# RTM_CON.net
KiCad netlist of a schematic drawn in Altium Designer
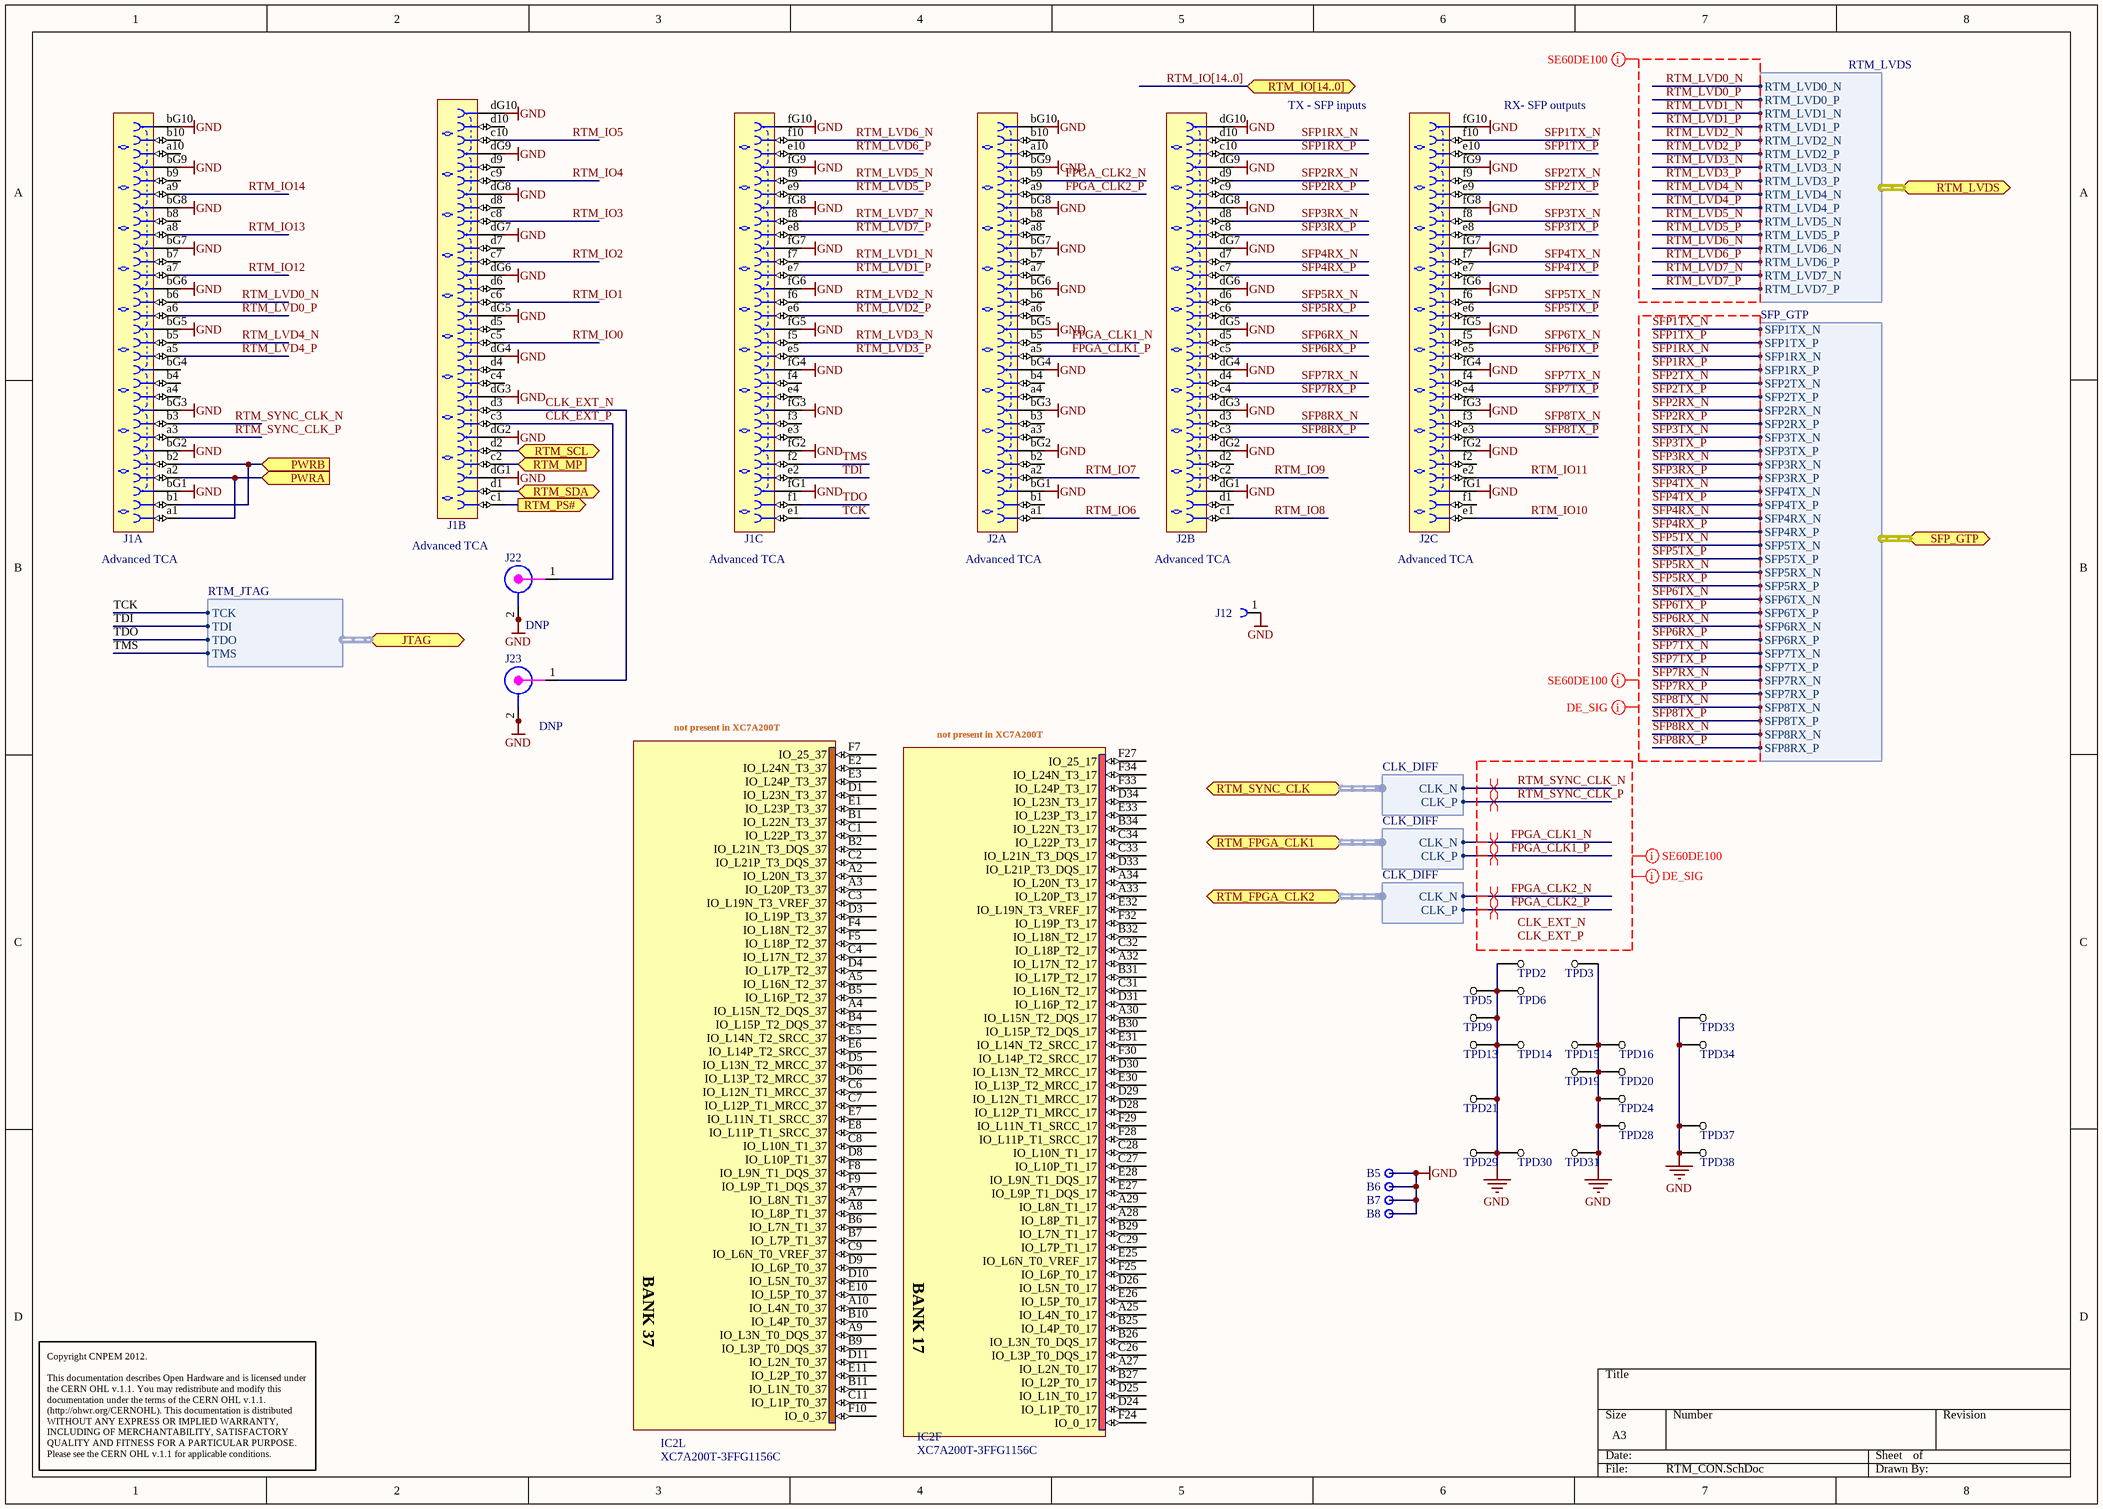
[diagram p0: RTM_CON.SchDoc]

(export (version "E")
  (design (tool "Eeschema 10.0.6"))
  (components
    (comp (ref "B5")
      (value "Test Point")
      (footprint "VERO_20-2136")
      (description "Single Terminal Socket")
      (fields
        (field (name "PART NUMBER") "VERO_20-2136")
        (field (name "MANUFACTURER") "VERO TECHNOLOGIES")
        (field (name "AUTHOR") "CERN DEM JLC")
      )
      (libsource (lib "Connectors") (part "Single Terminal Socket"))
    )
    (comp (ref "B6")
      (value "Test Point")
      (footprint "VERO_20-2136")
      (description "Single Terminal Socket")
      (fields
        (field (name "PART NUMBER") "VERO_20-2136")
        (field (name "MANUFACTURER") "VERO TECHNOLOGIES")
        (field (name "AUTHOR") "CERN DEM JLC")
      )
      (libsource (lib "Connectors") (part "Single Terminal Socket"))
    )
    (comp (ref "B7")
      (value "Test Point")
      (footprint "VERO_20-2136")
      (description "Single Terminal Socket")
      (fields
        (field (name "PART NUMBER") "VERO_20-2136")
        (field (name "MANUFACTURER") "VERO TECHNOLOGIES")
        (field (name "AUTHOR") "CERN DEM JLC")
      )
      (libsource (lib "Connectors") (part "Single Terminal Socket"))
    )
    (comp (ref "B8")
      (value "Test Point")
      (footprint "VERO_20-2136")
      (description "Single Terminal Socket")
      (fields
        (field (name "PART NUMBER") "VERO_20-2136")
        (field (name "MANUFACTURER") "VERO TECHNOLOGIES")
        (field (name "AUTHOR") "CERN DEM JLC")
      )
      (libsource (lib "Connectors") (part "Single Terminal Socket"))
    )
    (comp (ref "IC2")
      (value "XC7A200T-3FFG1156C")
      (footprint "BGA1156C100P34X34_3500X3500X335")
      (description "Artix-6 FPGA, 16 GTPs, 600 User I/Os, 1156-Pin BGA, Speed Grade 2, Commercial Grade, Pb-Free")
      (fields (field (name "MANUFACTURER") "XILINX") (field (name "AUTHOR") "CERN DEM JLC"))
      (libsource (lib "AMC_FMC_Carrier") (part "XC7A200T-3FFG1156C"))
    )
    (comp (ref "J1")
      (value "Advanced TCA")
      (footprint "TYCO_6469081-1")
      (description "Connector 60 ATCA Female 30 Pairs (60 Signals) + 3x10 Ground")
      (fields
        (field (name "PART NUMBER") "TYCO_6469081-1")
        (field (name "MANUFACTURER") "TYCO ELECTRONICS")
        (field (name "AUTHOR") "CERN DEM JLC")
      )
      (libsource (lib "Connectors") (part "Connector ATCA 60+30 Female"))
    )
    (comp (ref "J2")
      (value "Advanced TCA")
      (footprint "TYCO_6469081-1")
      (description "Connector 60 ATCA Female 30 Pairs (60 Signals) + 3x10 Ground")
      (fields
        (field (name "PART NUMBER") "TYCO_6469081-1")
        (field (name "MANUFACTURER") "TYCO ELECTRONICS")
        (field (name "AUTHOR") "CERN DEM JLC")
      )
      (libsource (lib "Connectors") (part "Connector ATCA 60+30 Female"))
    )
    (comp (ref "J12")
      (value "~")
      (footprint "TYCO_5120913-1")
      (description "Single Pin Female")
      (fields (field (name "PART NUMBER") "TYCO_5120913-1"))
      (libsource (lib "Connectors") (part "Single Pin Female"))
    )
    (comp (ref "J22")
      (value "DNP")
      (footprint "CON_UFL_HIROSE_RECEPTACLE")
      (description "UFL")
      (libsource (lib "LIBRARY_SCH") (part "CON_UFL_SMD"))
    )
    (comp (ref "J23")
      (value "DNP")
      (footprint "CON_UFL_HIROSE_RECEPTACLE")
      (description "UFL")
      (libsource (lib "LIBRARY_SCH") (part "CON_UFL_SMD"))
    )
    (comp (ref "TPD2")
      (value "Test Point")
      (footprint "TP_DIFF_0805")
      (description "1625854-2")
      (fields (field (name "PART NUMBER") "TP_DIFF"))
      (libsource (lib "Markers") (part "TP_SMD_DIFF"))
    )
    (comp (ref "TPD3")
      (value "Test Point")
      (footprint "TP_DIFF_0805")
      (description "1625854-2")
      (fields (field (name "PART NUMBER") "TP_DIFF"))
      (libsource (lib "Markers") (part "TP_SMD_DIFF"))
    )
    (comp (ref "TPD5")
      (value "Test Point")
      (footprint "TP_DIFF_0805")
      (description "1625854-2")
      (fields (field (name "PART NUMBER") "TP_DIFF"))
      (libsource (lib "Markers") (part "TP_SMD_DIFF"))
    )
    (comp (ref "TPD6")
      (value "Test Point")
      (footprint "TP_DIFF_0805")
      (description "1625854-2")
      (fields (field (name "PART NUMBER") "TP_DIFF"))
      (libsource (lib "Markers") (part "TP_SMD_DIFF"))
    )
    (comp (ref "TPD9")
      (value "Test Point")
      (footprint "TP_DIFF_0805")
      (description "1625854-2")
      (fields (field (name "PART NUMBER") "TP_DIFF"))
      (libsource (lib "Markers") (part "TP_SMD_DIFF"))
    )
    (comp (ref "TPD13")
      (value "Test Point")
      (footprint "TP_DIFF_0805")
      (description "1625854-2")
      (fields (field (name "PART NUMBER") "TP_DIFF"))
      (libsource (lib "Markers") (part "TP_SMD_DIFF"))
    )
    (comp (ref "TPD14")
      (value "Test Point")
      (footprint "TP_DIFF_0805")
      (description "1625854-2")
      (fields (field (name "PART NUMBER") "TP_DIFF"))
      (libsource (lib "Markers") (part "TP_SMD_DIFF"))
    )
    (comp (ref "TPD15")
      (value "Test Point")
      (footprint "TP_DIFF_0805")
      (description "1625854-2")
      (fields (field (name "PART NUMBER") "TP_DIFF"))
      (libsource (lib "Markers") (part "TP_SMD_DIFF"))
    )
    (comp (ref "TPD16")
      (value "Test Point")
      (footprint "TP_DIFF_0805")
      (description "1625854-2")
      (fields (field (name "PART NUMBER") "TP_DIFF"))
      (libsource (lib "Markers") (part "TP_SMD_DIFF"))
    )
    (comp (ref "TPD19")
      (value "Test Point")
      (footprint "TP_DIFF_0805")
      (description "1625854-2")
      (fields (field (name "PART NUMBER") "TP_DIFF"))
      (libsource (lib "Markers") (part "TP_SMD_DIFF"))
    )
    (comp (ref "TPD20")
      (value "Test Point")
      (footprint "TP_DIFF_0805")
      (description "1625854-2")
      (fields (field (name "PART NUMBER") "TP_DIFF"))
      (libsource (lib "Markers") (part "TP_SMD_DIFF"))
    )
    (comp (ref "TPD21")
      (value "Test Point")
      (footprint "TP_DIFF_0805")
      (description "1625854-2")
      (fields (field (name "PART NUMBER") "TP_DIFF"))
      (libsource (lib "Markers") (part "TP_SMD_DIFF"))
    )
    (comp (ref "TPD24")
      (value "Test Point")
      (footprint "TP_DIFF_0805")
      (description "1625854-2")
      (fields (field (name "PART NUMBER") "TP_DIFF"))
      (libsource (lib "Markers") (part "TP_SMD_DIFF"))
    )
    (comp (ref "TPD28")
      (value "Test Point")
      (footprint "TP_DIFF_0805")
      (description "1625854-2")
      (fields (field (name "PART NUMBER") "TP_DIFF"))
      (libsource (lib "Markers") (part "TP_SMD_DIFF"))
    )
    (comp (ref "TPD29")
      (value "Test Point")
      (footprint "TP_DIFF_0805")
      (description "1625854-2")
      (fields (field (name "PART NUMBER") "TP_DIFF"))
      (libsource (lib "Markers") (part "TP_SMD_DIFF"))
    )
    (comp (ref "TPD30")
      (value "Test Point")
      (footprint "TP_DIFF_0805")
      (description "1625854-2")
      (fields (field (name "PART NUMBER") "TP_DIFF"))
      (libsource (lib "Markers") (part "TP_SMD_DIFF"))
    )
    (comp (ref "TPD31")
      (value "Test Point")
      (footprint "TP_DIFF_0805")
      (description "1625854-2")
      (fields (field (name "PART NUMBER") "TP_DIFF"))
      (libsource (lib "Markers") (part "TP_SMD_DIFF"))
    )
    (comp (ref "TPD33")
      (value "Test Point")
      (footprint "TP_DIFF_0805")
      (description "1625854-2")
      (fields (field (name "PART NUMBER") "TP_DIFF"))
      (libsource (lib "Markers") (part "TP_SMD_DIFF"))
    )
    (comp (ref "TPD34")
      (value "Test Point")
      (footprint "TP_DIFF_0805")
      (description "1625854-2")
      (fields (field (name "PART NUMBER") "TP_DIFF"))
      (libsource (lib "Markers") (part "TP_SMD_DIFF"))
    )
    (comp (ref "TPD37")
      (value "Test Point")
      (footprint "TP_DIFF_0805")
      (description "1625854-2")
      (fields (field (name "PART NUMBER") "TP_DIFF"))
      (libsource (lib "Markers") (part "TP_SMD_DIFF"))
    )
    (comp (ref "TPD38")
      (value "Test Point")
      (footprint "TP_DIFF_0805")
      (description "1625854-2")
      (fields (field (name "PART NUMBER") "TP_DIFF"))
      (libsource (lib "Markers") (part "TP_SMD_DIFF"))
    )
  )
  (nets
    (net (code "5") (name "/CLK_EXT_N") (class "Default")
      (node (ref "J1") (pin "d3") (pinfunction "d3_d3") (pintype "bidirectional"))
      (node (ref "J23") (pin "1") (pintype "passive"))
    )
    (net (code "6") (name "/CLK_EXT_P") (class "Default")
      (node (ref "J1") (pin "c3") (pinfunction "c3_c3") (pintype "bidirectional"))
      (node (ref "J22") (pin "1") (pintype "passive"))
    )
    (net (code "7") (name "/FPGA_CLK1_N") (class "Default")
      (node (ref "J2") (pin "b5") (pinfunction "b5_b5") (pintype "bidirectional"))
    )
    (net (code "8") (name "/FPGA_CLK1_P") (class "Default")
      (node (ref "J2") (pin "a5") (pinfunction "a5_a5") (pintype "bidirectional"))
    )
    (net (code "9") (name "/FPGA_CLK2_N") (class "Default")
      (node (ref "J2") (pin "b9") (pinfunction "b9_b9") (pintype "bidirectional"))
    )
    (net (code "10") (name "/FPGA_CLK2_P") (class "Default")
      (node (ref "J2") (pin "a9") (pinfunction "a9_a9") (pintype "bidirectional"))
    )
    (net (code "11") (name "/PWRA") (class "Default")
      (node (ref "J1") (pin "a1") (pinfunction "a1_a1") (pintype "bidirectional"))
      (node (ref "J1") (pin "a2") (pinfunction "a2_a2") (pintype "bidirectional"))
    )
    (net (code "12") (name "/PWRB") (class "Default")
      (node (ref "J1") (pin "b1") (pinfunction "b1_b1") (pintype "bidirectional"))
      (node (ref "J1") (pin "b2") (pinfunction "b2_b2") (pintype "bidirectional"))
    )
    (net (code "13") (name "/RTM_IO0") (class "Default")
      (node (ref "J1") (pin "c5") (pinfunction "c5_c5") (pintype "bidirectional"))
    )
    (net (code "14") (name "/RTM_IO1") (class "Default")
      (node (ref "J1") (pin "c6") (pinfunction "c6_c6") (pintype "bidirectional"))
    )
    (net (code "15") (name "/RTM_IO2") (class "Default")
      (node (ref "J1") (pin "c7") (pinfunction "c7_c7") (pintype "bidirectional"))
    )
    (net (code "16") (name "/RTM_IO3") (class "Default")
      (node (ref "J1") (pin "c8") (pinfunction "c8_c8") (pintype "bidirectional"))
    )
    (net (code "17") (name "/RTM_IO4") (class "Default")
      (node (ref "J1") (pin "c9") (pinfunction "c9_c9") (pintype "bidirectional"))
    )
    (net (code "18") (name "/RTM_IO5") (class "Default")
      (node (ref "J1") (pin "c10") (pinfunction "c10_c10") (pintype "bidirectional"))
    )
    (net (code "19") (name "/RTM_IO6") (class "Default")
      (node (ref "J2") (pin "a1") (pinfunction "a1_a1") (pintype "bidirectional"))
    )
    (net (code "20") (name "/RTM_IO7") (class "Default")
      (node (ref "J2") (pin "a2") (pinfunction "a2_a2") (pintype "bidirectional"))
    )
    (net (code "21") (name "/RTM_IO8") (class "Default")
      (node (ref "J2") (pin "c1") (pinfunction "c1_c1") (pintype "bidirectional"))
    )
    (net (code "22") (name "/RTM_IO9") (class "Default")
      (node (ref "J2") (pin "c2") (pinfunction "c2_c2") (pintype "bidirectional"))
    )
    (net (code "23") (name "/RTM_IO10") (class "Default")
      (node (ref "J2") (pin "e1") (pinfunction "e1_e1") (pintype "bidirectional"))
    )
    (net (code "24") (name "/RTM_IO11") (class "Default")
      (node (ref "J2") (pin "e2") (pinfunction "e2_e2") (pintype "bidirectional"))
    )
    (net (code "25") (name "/RTM_IO12") (class "Default")
      (node (ref "J1") (pin "a7") (pinfunction "a7_a7") (pintype "bidirectional"))
    )
    (net (code "26") (name "/RTM_IO13") (class "Default")
      (node (ref "J1") (pin "a8") (pinfunction "a8_a8") (pintype "bidirectional"))
    )
    (net (code "27") (name "/RTM_IO14") (class "Default")
      (node (ref "J1") (pin "a9") (pinfunction "a9_a9") (pintype "bidirectional"))
    )
    (net (code "29") (name "/RTM_LVD0_N") (class "Default")
      (node (ref "J1") (pin "b6") (pinfunction "b6_b6") (pintype "bidirectional"))
    )
    (net (code "30") (name "/RTM_LVD0_P") (class "Default")
      (node (ref "J1") (pin "a6") (pinfunction "a6_a6") (pintype "bidirectional"))
    )
    (net (code "31") (name "/RTM_LVD1_N") (class "Default")
      (node (ref "J1") (pin "f7") (pinfunction "f7_f7") (pintype "bidirectional"))
    )
    (net (code "32") (name "/RTM_LVD1_P") (class "Default")
      (node (ref "J1") (pin "e7") (pinfunction "e7_e7") (pintype "bidirectional"))
    )
    (net (code "33") (name "/RTM_LVD2_N") (class "Default")
      (node (ref "J1") (pin "f6") (pinfunction "f6_f6") (pintype "bidirectional"))
    )
    (net (code "34") (name "/RTM_LVD2_P") (class "Default")
      (node (ref "J1") (pin "e6") (pinfunction "e6_e6") (pintype "bidirectional"))
    )
    (net (code "35") (name "/RTM_LVD3_N") (class "Default")
      (node (ref "J1") (pin "f5") (pinfunction "f5_f5") (pintype "bidirectional"))
    )
    (net (code "36") (name "/RTM_LVD3_P") (class "Default")
      (node (ref "J1") (pin "e5") (pinfunction "e5_e5") (pintype "bidirectional"))
    )
    (net (code "37") (name "/RTM_LVD4_N") (class "Default")
      (node (ref "J1") (pin "b5") (pinfunction "b5_b5") (pintype "bidirectional"))
    )
    (net (code "38") (name "/RTM_LVD4_P") (class "Default")
      (node (ref "J1") (pin "a5") (pinfunction "a5_a5") (pintype "bidirectional"))
    )
    (net (code "39") (name "/RTM_LVD5_N") (class "Default")
      (node (ref "J1") (pin "f9") (pinfunction "f9_f9") (pintype "bidirectional"))
    )
    (net (code "40") (name "/RTM_LVD5_P") (class "Default")
      (node (ref "J1") (pin "e9") (pinfunction "e9_e9") (pintype "bidirectional"))
    )
    (net (code "41") (name "/RTM_LVD6_N") (class "Default")
      (node (ref "J1") (pin "f10") (pinfunction "f10_f10") (pintype "bidirectional"))
    )
    (net (code "42") (name "/RTM_LVD6_P") (class "Default")
      (node (ref "J1") (pin "e10") (pinfunction "e10_e10") (pintype "bidirectional"))
    )
    (net (code "43") (name "/RTM_LVD7_N") (class "Default")
      (node (ref "J1") (pin "f8") (pinfunction "f8_f8") (pintype "bidirectional"))
    )
    (net (code "44") (name "/RTM_LVD7_P") (class "Default")
      (node (ref "J1") (pin "e8") (pinfunction "e8_e8") (pintype "bidirectional"))
    )
    (net (code "45") (name "/RTM_MP") (class "Default")
      (node (ref "J1") (pin "c2") (pinfunction "c2_c2") (pintype "bidirectional"))
    )
    (net (code "46") (name "/RTM_PS#") (class "Default")
      (node (ref "J1") (pin "c1") (pinfunction "c1_c1") (pintype "bidirectional"))
    )
    (net (code "47") (name "/RTM_SCL") (class "Default")
      (node (ref "J1") (pin "d2") (pinfunction "d2_d2") (pintype "bidirectional"))
    )
    (net (code "48") (name "/RTM_SDA") (class "Default")
      (node (ref "J1") (pin "d1") (pinfunction "d1_d1") (pintype "bidirectional"))
    )
    (net (code "49") (name "/RTM_SYNC_CLK_N") (class "Default")
      (node (ref "J1") (pin "b3") (pinfunction "b3_b3") (pintype "bidirectional"))
    )
    (net (code "50") (name "/RTM_SYNC_CLK_P") (class "Default")
      (node (ref "J1") (pin "a3") (pinfunction "a3_a3") (pintype "bidirectional"))
    )
    (net (code "51") (name "/SFP1RX_N") (class "Default")
      (node (ref "J2") (pin "d10") (pinfunction "d10_d10") (pintype "bidirectional"))
    )
    (net (code "52") (name "/SFP1RX_P") (class "Default")
      (node (ref "J2") (pin "c10") (pinfunction "c10_c10") (pintype "bidirectional"))
    )
    (net (code "53") (name "/SFP1TX_N") (class "Default")
      (node (ref "J2") (pin "f10") (pinfunction "f10_f10") (pintype "bidirectional"))
    )
    (net (code "54") (name "/SFP1TX_P") (class "Default")
      (node (ref "J2") (pin "e10") (pinfunction "e10_e10") (pintype "bidirectional"))
    )
    (net (code "55") (name "/SFP2RX_N") (class "Default")
      (node (ref "J2") (pin "d9") (pinfunction "d9_d9") (pintype "bidirectional"))
    )
    (net (code "56") (name "/SFP2RX_P") (class "Default")
      (node (ref "J2") (pin "c9") (pinfunction "c9_c9") (pintype "bidirectional"))
    )
    (net (code "57") (name "/SFP2TX_N") (class "Default")
      (node (ref "J2") (pin "f9") (pinfunction "f9_f9") (pintype "bidirectional"))
    )
    (net (code "58") (name "/SFP2TX_P") (class "Default")
      (node (ref "J2") (pin "e9") (pinfunction "e9_e9") (pintype "bidirectional"))
    )
    (net (code "59") (name "/SFP3RX_N") (class "Default")
      (node (ref "J2") (pin "d8") (pinfunction "d8_d8") (pintype "bidirectional"))
    )
    (net (code "60") (name "/SFP3RX_P") (class "Default")
      (node (ref "J2") (pin "c8") (pinfunction "c8_c8") (pintype "bidirectional"))
    )
    (net (code "61") (name "/SFP3TX_N") (class "Default")
      (node (ref "J2") (pin "f8") (pinfunction "f8_f8") (pintype "bidirectional"))
    )
    (net (code "62") (name "/SFP3TX_P") (class "Default")
      (node (ref "J2") (pin "e8") (pinfunction "e8_e8") (pintype "bidirectional"))
    )
    (net (code "63") (name "/SFP4RX_N") (class "Default")
      (node (ref "J2") (pin "d7") (pinfunction "d7_d7") (pintype "bidirectional"))
    )
    (net (code "64") (name "/SFP4RX_P") (class "Default")
      (node (ref "J2") (pin "c7") (pinfunction "c7_c7") (pintype "bidirectional"))
    )
    (net (code "65") (name "/SFP4TX_N") (class "Default")
      (node (ref "J2") (pin "f7") (pinfunction "f7_f7") (pintype "bidirectional"))
    )
    (net (code "66") (name "/SFP4TX_P") (class "Default")
      (node (ref "J2") (pin "e7") (pinfunction "e7_e7") (pintype "bidirectional"))
    )
    (net (code "67") (name "/SFP5RX_N") (class "Default")
      (node (ref "J2") (pin "d6") (pinfunction "d6_d6") (pintype "bidirectional"))
    )
    (net (code "68") (name "/SFP5RX_P") (class "Default")
      (node (ref "J2") (pin "c6") (pinfunction "c6_c6") (pintype "bidirectional"))
    )
    (net (code "69") (name "/SFP5TX_N") (class "Default")
      (node (ref "J2") (pin "f6") (pinfunction "f6_f6") (pintype "bidirectional"))
    )
    (net (code "70") (name "/SFP5TX_P") (class "Default")
      (node (ref "J2") (pin "e6") (pinfunction "e6_e6") (pintype "bidirectional"))
    )
    (net (code "71") (name "/SFP6RX_N") (class "Default")
      (node (ref "J2") (pin "d5") (pinfunction "d5_d5") (pintype "bidirectional"))
    )
    (net (code "72") (name "/SFP6RX_P") (class "Default")
      (node (ref "J2") (pin "c5") (pinfunction "c5_c5") (pintype "bidirectional"))
    )
    (net (code "73") (name "/SFP6TX_N") (class "Default")
      (node (ref "J2") (pin "f5") (pinfunction "f5_f5") (pintype "bidirectional"))
    )
    (net (code "74") (name "/SFP6TX_P") (class "Default")
      (node (ref "J2") (pin "e5") (pinfunction "e5_e5") (pintype "bidirectional"))
    )
    (net (code "75") (name "/SFP7RX_N") (class "Default")
      (node (ref "J2") (pin "d4") (pinfunction "d4_d4") (pintype "bidirectional"))
    )
    (net (code "76") (name "/SFP7RX_P") (class "Default")
      (node (ref "J2") (pin "c4") (pinfunction "c4_c4") (pintype "bidirectional"))
    )
    (net (code "77") (name "/SFP7TX_N") (class "Default")
      (node (ref "J2") (pin "f4") (pinfunction "f4_f4") (pintype "bidirectional"))
    )
    (net (code "78") (name "/SFP7TX_P") (class "Default")
      (node (ref "J2") (pin "e4") (pinfunction "e4_e4") (pintype "bidirectional"))
    )
    (net (code "79") (name "/SFP8RX_N") (class "Default")
      (node (ref "J2") (pin "d3") (pinfunction "d3_d3") (pintype "bidirectional"))
    )
    (net (code "80") (name "/SFP8RX_P") (class "Default")
      (node (ref "J2") (pin "c3") (pinfunction "c3_c3") (pintype "bidirectional"))
    )
    (net (code "81") (name "/SFP8TX_N") (class "Default")
      (node (ref "J2") (pin "f3") (pinfunction "f3_f3") (pintype "bidirectional"))
    )
    (net (code "82") (name "/SFP8TX_P") (class "Default")
      (node (ref "J2") (pin "e3") (pinfunction "e3_e3") (pintype "bidirectional"))
    )
    (net (code "83") (name "/TCK") (class "Default")
      (node (ref "J1") (pin "e1") (pinfunction "e1_e1") (pintype "bidirectional"))
    )
    (net (code "84") (name "/TDI") (class "Default")
      (node (ref "J1") (pin "e2") (pinfunction "e2_e2") (pintype "bidirectional"))
    )
    (net (code "85") (name "/TDO") (class "Default")
      (node (ref "J1") (pin "f1") (pinfunction "f1_f1") (pintype "bidirectional"))
    )
    (net (code "86") (name "/TMS") (class "Default")
      (node (ref "J1") (pin "f2") (pinfunction "f2_f2") (pintype "bidirectional"))
    )
    (net (code "91") (name "GND") (class "Default")
      (node (ref "B5") (pin "1") (pinfunction "1_1") (pintype "bidirectional"))
      (node (ref "B6") (pin "1") (pinfunction "1_1") (pintype "bidirectional"))
      (node (ref "B7") (pin "1") (pinfunction "1_1") (pintype "bidirectional"))
      (node (ref "B8") (pin "1") (pinfunction "1_1") (pintype "bidirectional"))
      (node (ref "J1") (pin "bG1") (pinfunction "bG1_bG1") (pintype "power_in"))
      (node (ref "J1") (pin "bG10") (pinfunction "bG10_bG10") (pintype "power_in"))
      (node (ref "J1") (pin "bG2") (pinfunction "bG2_bG2") (pintype "power_in"))
      (node (ref "J1") (pin "bG3") (pinfunction "bG3_bG3") (pintype "power_in"))
      (node (ref "J1") (pin "bG5") (pinfunction "bG5_bG5") (pintype "power_in"))
      (node (ref "J1") (pin "bG6") (pinfunction "bG6_bG6") (pintype "power_in"))
      (node (ref "J1") (pin "bG7") (pinfunction "bG7_bG7") (pintype "power_in"))
      (node (ref "J1") (pin "bG8") (pinfunction "bG8_bG8") (pintype "power_in"))
      (node (ref "J1") (pin "bG9") (pinfunction "bG9_bG9") (pintype "power_in"))
      (node (ref "J1") (pin "dG1") (pinfunction "dG1_dG1") (pintype "power_in"))
      (node (ref "J1") (pin "dG10") (pinfunction "dG10_dG10") (pintype "power_in"))
      (node (ref "J1") (pin "dG2") (pinfunction "dG2_dG2") (pintype "power_in"))
      (node (ref "J1") (pin "dG3") (pinfunction "dG3_dG3") (pintype "power_in"))
      (node (ref "J1") (pin "dG4") (pinfunction "dG4_dG4") (pintype "power_in"))
      (node (ref "J1") (pin "dG5") (pinfunction "dG5_dG5") (pintype "power_in"))
      (node (ref "J1") (pin "dG6") (pinfunction "dG6_dG6") (pintype "power_in"))
      (node (ref "J1") (pin "dG7") (pinfunction "dG7_dG7") (pintype "power_in"))
      (node (ref "J1") (pin "dG8") (pinfunction "dG8_dG8") (pintype "power_in"))
      (node (ref "J1") (pin "dG9") (pinfunction "dG9_dG9") (pintype "power_in"))
      (node (ref "J1") (pin "fG1") (pinfunction "fG1_fG1") (pintype "power_in"))
      (node (ref "J1") (pin "fG10") (pinfunction "fG10_fG10") (pintype "power_in"))
      (node (ref "J1") (pin "fG2") (pinfunction "fG2_fG2") (pintype "power_in"))
      (node (ref "J1") (pin "fG3") (pinfunction "fG3_fG3") (pintype "power_in"))
      (node (ref "J1") (pin "fG4") (pinfunction "fG4_fG4") (pintype "power_in"))
      (node (ref "J1") (pin "fG5") (pinfunction "fG5_fG5") (pintype "power_in"))
      (node (ref "J1") (pin "fG6") (pinfunction "fG6_fG6") (pintype "power_in"))
      (node (ref "J1") (pin "fG7") (pinfunction "fG7_fG7") (pintype "power_in"))
      (node (ref "J1") (pin "fG8") (pinfunction "fG8_fG8") (pintype "power_in"))
      (node (ref "J1") (pin "fG9") (pinfunction "fG9_fG9") (pintype "power_in"))
      (node (ref "J12") (pin "1") (pinfunction "1_1") (pintype "bidirectional"))
      (node (ref "J2") (pin "bG1") (pinfunction "bG1_bG1") (pintype "power_in"))
      (node (ref "J2") (pin "bG10") (pinfunction "bG10_bG10") (pintype "power_in"))
      (node (ref "J2") (pin "bG2") (pinfunction "bG2_bG2") (pintype "power_in"))
      (node (ref "J2") (pin "bG3") (pinfunction "bG3_bG3") (pintype "power_in"))
      (node (ref "J2") (pin "bG4") (pinfunction "bG4_bG4") (pintype "power_in"))
      (node (ref "J2") (pin "bG5") (pinfunction "bG5_bG5") (pintype "power_in"))
      (node (ref "J2") (pin "bG6") (pinfunction "bG6_bG6") (pintype "power_in"))
      (node (ref "J2") (pin "bG7") (pinfunction "bG7_bG7") (pintype "power_in"))
      (node (ref "J2") (pin "bG8") (pinfunction "bG8_bG8") (pintype "power_in"))
      (node (ref "J2") (pin "bG9") (pinfunction "bG9_bG9") (pintype "power_in"))
      (node (ref "J2") (pin "dG1") (pinfunction "dG1_dG1") (pintype "power_in"))
      (node (ref "J2") (pin "dG10") (pinfunction "dG10_dG10") (pintype "power_in"))
      (node (ref "J2") (pin "dG2") (pinfunction "dG2_dG2") (pintype "power_in"))
      (node (ref "J2") (pin "dG3") (pinfunction "dG3_dG3") (pintype "power_in"))
      (node (ref "J2") (pin "dG4") (pinfunction "dG4_dG4") (pintype "power_in"))
      (node (ref "J2") (pin "dG5") (pinfunction "dG5_dG5") (pintype "power_in"))
      (node (ref "J2") (pin "dG6") (pinfunction "dG6_dG6") (pintype "power_in"))
      (node (ref "J2") (pin "dG7") (pinfunction "dG7_dG7") (pintype "power_in"))
      (node (ref "J2") (pin "dG8") (pinfunction "dG8_dG8") (pintype "power_in"))
      (node (ref "J2") (pin "dG9") (pinfunction "dG9_dG9") (pintype "power_in"))
      (node (ref "J2") (pin "fG1") (pinfunction "fG1_fG1") (pintype "power_in"))
      (node (ref "J2") (pin "fG10") (pinfunction "fG10_fG10") (pintype "power_in"))
      (node (ref "J2") (pin "fG2") (pinfunction "fG2_fG2") (pintype "power_in"))
      (node (ref "J2") (pin "fG3") (pinfunction "fG3_fG3") (pintype "power_in"))
      (node (ref "J2") (pin "fG4") (pinfunction "fG4_fG4") (pintype "power_in"))
      (node (ref "J2") (pin "fG5") (pinfunction "fG5_fG5") (pintype "power_in"))
      (node (ref "J2") (pin "fG6") (pinfunction "fG6_fG6") (pintype "power_in"))
      (node (ref "J2") (pin "fG7") (pinfunction "fG7_fG7") (pintype "power_in"))
      (node (ref "J2") (pin "fG8") (pinfunction "fG8_fG8") (pintype "power_in"))
      (node (ref "J2") (pin "fG9") (pinfunction "fG9_fG9") (pintype "power_in"))
      (node (ref "J22") (pin "2") (pintype "passive"))
      (node (ref "J22") (pin "2a") (pinfunction "GND_2a") (pintype "passive"))
      (node (ref "J23") (pin "2") (pintype "passive"))
      (node (ref "J23") (pin "2a") (pinfunction "GND_2a") (pintype "passive"))
      (node (ref "TPD13") (pin "1") (pinfunction "TP_1") (pintype "passive"))
      (node (ref "TPD14") (pin "1") (pinfunction "TP_1") (pintype "passive"))
      (node (ref "TPD15") (pin "1") (pinfunction "TP_1") (pintype "passive"))
      (node (ref "TPD16") (pin "1") (pinfunction "TP_1") (pintype "passive"))
      (node (ref "TPD19") (pin "1") (pinfunction "TP_1") (pintype "passive"))
      (node (ref "TPD2") (pin "1") (pinfunction "TP_1") (pintype "passive"))
      (node (ref "TPD20") (pin "1") (pinfunction "TP_1") (pintype "passive"))
      (node (ref "TPD21") (pin "1") (pinfunction "TP_1") (pintype "passive"))
      (node (ref "TPD24") (pin "1") (pinfunction "TP_1") (pintype "passive"))
      (node (ref "TPD28") (pin "1") (pinfunction "TP_1") (pintype "passive"))
      (node (ref "TPD29") (pin "1") (pinfunction "TP_1") (pintype "passive"))
      (node (ref "TPD3") (pin "1") (pinfunction "TP_1") (pintype "passive"))
      (node (ref "TPD30") (pin "1") (pinfunction "TP_1") (pintype "passive"))
      (node (ref "TPD31") (pin "1") (pinfunction "TP_1") (pintype "passive"))
      (node (ref "TPD33") (pin "1") (pinfunction "TP_1") (pintype "passive"))
      (node (ref "TPD34") (pin "1") (pinfunction "TP_1") (pintype "passive"))
      (node (ref "TPD37") (pin "1") (pinfunction "TP_1") (pintype "passive"))
      (node (ref "TPD38") (pin "1") (pinfunction "TP_1") (pintype "passive"))
      (node (ref "TPD5") (pin "1") (pinfunction "TP_1") (pintype "passive"))
      (node (ref "TPD6") (pin "1") (pinfunction "TP_1") (pintype "passive"))
      (node (ref "TPD9") (pin "1") (pinfunction "TP_1") (pintype "passive"))
    )
    (net (code "92") (name "unconnected-(IC2F-IO_0_17-PadF24)") (class "Default")
      (node (ref "IC2") (pin "F24") (pinfunction "IO_0_17_F24") (pintype "bidirectional"))
    )
    (net (code "93") (name "unconnected-(IC2F-IO_25_17-PadF27)") (class "Default")
      (node (ref "IC2") (pin "F27") (pinfunction "IO_25_17_F27") (pintype "bidirectional"))
    )
    (net (code "94") (name "unconnected-(IC2F-IO_L1N_T0_17-PadD25)") (class "Default")
      (node (ref "IC2") (pin "D25") (pinfunction "IO_L1N_T0_17_D25") (pintype "bidirectional"))
    )
    (net (code "95") (name "unconnected-(IC2F-IO_L1P_T0_17-PadD24)") (class "Default")
      (node (ref "IC2") (pin "D24") (pinfunction "IO_L1P_T0_17_D24") (pintype "bidirectional"))
    )
    (net (code "96") (name "unconnected-(IC2F-IO_L2N_T0_17-PadA27)") (class "Default")
      (node (ref "IC2") (pin "A27") (pinfunction "IO_L2N_T0_17_A27") (pintype "bidirectional"))
    )
    (net (code "97") (name "unconnected-(IC2F-IO_L2P_T0_17-PadB27)") (class "Default")
      (node (ref "IC2") (pin "B27") (pinfunction "IO_L2P_T0_17_B27") (pintype "bidirectional"))
    )
    (net (code "98") (name "unconnected-(IC2F-IO_L3N_T0_DQS_17-PadB26)") (class "Default")
      (node (ref "IC2") (pin "B26") (pinfunction "IO_L3N_T0_DQS_17_B26") (pintype "bidirectional"))
    )
    (net (code "99") (name "unconnected-(IC2F-IO_L3P_T0_DQS_17-PadC26)") (class "Default")
      (node (ref "IC2") (pin "C26") (pinfunction "IO_L3P_T0_DQS_17_C26") (pintype "bidirectional"))
    )
    (net (code "100") (name "unconnected-(IC2F-IO_L4N_T0_17-PadA25)") (class "Default")
      (node (ref "IC2") (pin "A25") (pinfunction "IO_L4N_T0_17_A25") (pintype "bidirectional"))
    )
    (net (code "101") (name "unconnected-(IC2F-IO_L4P_T0_17-PadB25)") (class "Default")
      (node (ref "IC2") (pin "B25") (pinfunction "IO_L4P_T0_17_B25") (pintype "bidirectional"))
    )
    (net (code "102") (name "unconnected-(IC2F-IO_L5N_T0_17-PadD26)") (class "Default")
      (node (ref "IC2") (pin "D26") (pinfunction "IO_L5N_T0_17_D26") (pintype "bidirectional"))
    )
    (net (code "103") (name "unconnected-(IC2F-IO_L5P_T0_17-PadE26)") (class "Default")
      (node (ref "IC2") (pin "E26") (pinfunction "IO_L5P_T0_17_E26") (pintype "bidirectional"))
    )
    (net (code "104") (name "unconnected-(IC2F-IO_L6N_T0_VREF_17-PadE25)") (class "Default")
      (node (ref "IC2") (pin "E25") (pinfunction "IO_L6N_T0_VREF_17_E25") (pintype "bidirectional"))
    )
    (net (code "105") (name "unconnected-(IC2F-IO_L6P_T0_17-PadF25)") (class "Default")
      (node (ref "IC2") (pin "F25") (pinfunction "IO_L6P_T0_17_F25") (pintype "bidirectional"))
    )
    (net (code "106") (name "unconnected-(IC2F-IO_L7N_T1_17-PadB29)") (class "Default")
      (node (ref "IC2") (pin "B29") (pinfunction "IO_L7N_T1_17_B29") (pintype "bidirectional"))
    )
    (net (code "107") (name "unconnected-(IC2F-IO_L7P_T1_17-PadC29)") (class "Default")
      (node (ref "IC2") (pin "C29") (pinfunction "IO_L7P_T1_17_C29") (pintype "bidirectional"))
    )
    (net (code "108") (name "unconnected-(IC2F-IO_L8N_T1_17-PadA29)") (class "Default")
      (node (ref "IC2") (pin "A29") (pinfunction "IO_L8N_T1_17_A29") (pintype "bidirectional"))
    )
    (net (code "109") (name "unconnected-(IC2F-IO_L8P_T1_17-PadA28)") (class "Default")
      (node (ref "IC2") (pin "A28") (pinfunction "IO_L8P_T1_17_A28") (pintype "bidirectional"))
    )
    (net (code "110") (name "unconnected-(IC2F-IO_L9N_T1_DQS_17-PadE28)") (class "Default")
      (node (ref "IC2") (pin "E28") (pinfunction "IO_L9N_T1_DQS_17_E28") (pintype "bidirectional"))
    )
    (net (code "111") (name "unconnected-(IC2F-IO_L9P_T1_DQS_17-PadE27)") (class "Default")
      (node (ref "IC2") (pin "E27") (pinfunction "IO_L9P_T1_DQS_17_E27") (pintype "bidirectional"))
    )
    (net (code "112") (name "unconnected-(IC2F-IO_L10N_T1_17-PadC28)") (class "Default")
      (node (ref "IC2") (pin "C28") (pinfunction "IO_L10N_T1_17_C28") (pintype "bidirectional"))
    )
    (net (code "113") (name "unconnected-(IC2F-IO_L10P_T1_17-PadC27)") (class "Default")
      (node (ref "IC2") (pin "C27") (pinfunction "IO_L10P_T1_17_C27") (pintype "bidirectional"))
    )
    (net (code "114") (name "unconnected-(IC2F-IO_L11N_T1_SRCC_17-PadF29)") (class "Default")
      (node (ref "IC2") (pin "F29") (pinfunction "IO_L11N_T1_SRCC_17_F29") (pintype "bidirectional"))
    )
    (net (code "115") (name "unconnected-(IC2F-IO_L11P_T1_SRCC_17-PadF28)") (class "Default")
      (node (ref "IC2") (pin "F28") (pinfunction "IO_L11P_T1_SRCC_17_F28") (pintype "bidirectional"))
    )
    (net (code "116") (name "unconnected-(IC2F-IO_L12N_T1_MRCC_17-PadD29)") (class "Default")
      (node (ref "IC2") (pin "D29") (pinfunction "IO_L12N_T1_MRCC_17_D29") (pintype "bidirectional"))
    )
    (net (code "117") (name "unconnected-(IC2F-IO_L12P_T1_MRCC_17-PadD28)") (class "Default")
      (node (ref "IC2") (pin "D28") (pinfunction "IO_L12P_T1_MRCC_17_D28") (pintype "bidirectional"))
    )
    (net (code "118") (name "unconnected-(IC2F-IO_L13N_T2_MRCC_17-PadD30)") (class "Default")
      (node (ref "IC2") (pin "D30") (pinfunction "IO_L13N_T2_MRCC_17_D30") (pintype "bidirectional"))
    )
    (net (code "119") (name "unconnected-(IC2F-IO_L13P_T2_MRCC_17-PadE30)") (class "Default")
      (node (ref "IC2") (pin "E30") (pinfunction "IO_L13P_T2_MRCC_17_E30") (pintype "bidirectional"))
    )
    (net (code "120") (name "unconnected-(IC2F-IO_L14N_T2_SRCC_17-PadE31)") (class "Default")
      (node (ref "IC2") (pin "E31") (pinfunction "IO_L14N_T2_SRCC_17_E31") (pintype "bidirectional"))
    )
    (net (code "121") (name "unconnected-(IC2F-IO_L14P_T2_SRCC_17-PadF30)") (class "Default")
      (node (ref "IC2") (pin "F30") (pinfunction "IO_L14P_T2_SRCC_17_F30") (pintype "bidirectional"))
    )
    (net (code "122") (name "unconnected-(IC2F-IO_L15N_T2_DQS_17-PadA30)") (class "Default")
      (node (ref "IC2") (pin "A30") (pinfunction "IO_L15N_T2_DQS_17_A30") (pintype "bidirectional"))
    )
    (net (code "123") (name "unconnected-(IC2F-IO_L15P_T2_DQS_17-PadB30)") (class "Default")
      (node (ref "IC2") (pin "B30") (pinfunction "IO_L15P_T2_DQS_17_B30") (pintype "bidirectional"))
    )
    (net (code "124") (name "unconnected-(IC2F-IO_L16N_T2_17-PadC31)") (class "Default")
      (node (ref "IC2") (pin "C31") (pinfunction "IO_L16N_T2_17_C31") (pintype "bidirectional"))
    )
    (net (code "125") (name "unconnected-(IC2F-IO_L16P_T2_17-PadD31)") (class "Default")
      (node (ref "IC2") (pin "D31") (pinfunction "IO_L16P_T2_17_D31") (pintype "bidirectional"))
    )
    (net (code "126") (name "unconnected-(IC2F-IO_L17N_T2_17-PadA32)") (class "Default")
      (node (ref "IC2") (pin "A32") (pinfunction "IO_L17N_T2_17_A32") (pintype "bidirectional"))
    )
    (net (code "127") (name "unconnected-(IC2F-IO_L17P_T2_17-PadB31)") (class "Default")
      (node (ref "IC2") (pin "B31") (pinfunction "IO_L17P_T2_17_B31") (pintype "bidirectional"))
    )
    (net (code "128") (name "unconnected-(IC2F-IO_L18N_T2_17-PadB32)") (class "Default")
      (node (ref "IC2") (pin "B32") (pinfunction "IO_L18N_T2_17_B32") (pintype "bidirectional"))
    )
    (net (code "129") (name "unconnected-(IC2F-IO_L18P_T2_17-PadC32)") (class "Default")
      (node (ref "IC2") (pin "C32") (pinfunction "IO_L18P_T2_17_C32") (pintype "bidirectional"))
    )
    (net (code "130") (name "unconnected-(IC2F-IO_L19N_T3_VREF_17-PadE32)") (class "Default")
      (node (ref "IC2") (pin "E32") (pinfunction "IO_L19N_T3_VREF_17_E32") (pintype "bidirectional"))
    )
    (net (code "131") (name "unconnected-(IC2F-IO_L19P_T3_17-PadF32)") (class "Default")
      (node (ref "IC2") (pin "F32") (pinfunction "IO_L19P_T3_17_F32") (pintype "bidirectional"))
    )
    (net (code "132") (name "unconnected-(IC2F-IO_L20N_T3_17-PadA34)") (class "Default")
      (node (ref "IC2") (pin "A34") (pinfunction "IO_L20N_T3_17_A34") (pintype "bidirectional"))
    )
    (net (code "133") (name "unconnected-(IC2F-IO_L20P_T3_17-PadA33)") (class "Default")
      (node (ref "IC2") (pin "A33") (pinfunction "IO_L20P_T3_17_A33") (pintype "bidirectional"))
    )
    (net (code "134") (name "unconnected-(IC2F-IO_L21N_T3_DQS_17-PadC33)") (class "Default")
      (node (ref "IC2") (pin "C33") (pinfunction "IO_L21N_T3_DQS_17_C33") (pintype "bidirectional"))
    )
    (net (code "135") (name "unconnected-(IC2F-IO_L21P_T3_DQS_17-PadD33)") (class "Default")
      (node (ref "IC2") (pin "D33") (pinfunction "IO_L21P_T3_DQS_17_D33") (pintype "bidirectional"))
    )
    (net (code "136") (name "unconnected-(IC2F-IO_L22N_T3_17-PadB34)") (class "Default")
      (node (ref "IC2") (pin "B34") (pinfunction "IO_L22N_T3_17_B34") (pintype "bidirectional"))
    )
    (net (code "137") (name "unconnected-(IC2F-IO_L22P_T3_17-PadC34)") (class "Default")
      (node (ref "IC2") (pin "C34") (pinfunction "IO_L22P_T3_17_C34") (pintype "bidirectional"))
    )
    (net (code "138") (name "unconnected-(IC2F-IO_L23N_T3_17-PadD34)") (class "Default")
      (node (ref "IC2") (pin "D34") (pinfunction "IO_L23N_T3_17_D34") (pintype "bidirectional"))
    )
    (net (code "139") (name "unconnected-(IC2F-IO_L23P_T3_17-PadE33)") (class "Default")
      (node (ref "IC2") (pin "E33") (pinfunction "IO_L23P_T3_17_E33") (pintype "bidirectional"))
    )
    (net (code "140") (name "unconnected-(IC2F-IO_L24N_T3_17-PadF34)") (class "Default")
      (node (ref "IC2") (pin "F34") (pinfunction "IO_L24N_T3_17_F34") (pintype "bidirectional"))
    )
    (net (code "141") (name "unconnected-(IC2F-IO_L24P_T3_17-PadF33)") (class "Default")
      (node (ref "IC2") (pin "F33") (pinfunction "IO_L24P_T3_17_F33") (pintype "bidirectional"))
    )
    (net (code "142") (name "unconnected-(IC2L-IO_0_37-PadF10)") (class "Default")
      (node (ref "IC2") (pin "F10") (pinfunction "IO_0_37_F10") (pintype "bidirectional"))
    )
    (net (code "143") (name "unconnected-(IC2L-IO_25_37-PadF7)") (class "Default")
      (node (ref "IC2") (pin "F7") (pinfunction "IO_25_37_F7") (pintype "bidirectional"))
    )
    (net (code "144") (name "unconnected-(IC2L-IO_L1N_T0_37-PadB11)") (class "Default")
      (node (ref "IC2") (pin "B11") (pinfunction "IO_L1N_T0_37_B11") (pintype "bidirectional"))
    )
    (net (code "145") (name "unconnected-(IC2L-IO_L1P_T0_37-PadC11)") (class "Default")
      (node (ref "IC2") (pin "C11") (pinfunction "IO_L1P_T0_37_C11") (pintype "bidirectional"))
    )
    (net (code "146") (name "unconnected-(IC2L-IO_L2N_T0_37-PadD11)") (class "Default")
      (node (ref "IC2") (pin "D11") (pinfunction "IO_L2N_T0_37_D11") (pintype "bidirectional"))
    )
    (net (code "147") (name "unconnected-(IC2L-IO_L2P_T0_37-PadE11)") (class "Default")
      (node (ref "IC2") (pin "E11") (pinfunction "IO_L2P_T0_37_E11") (pintype "bidirectional"))
    )
    (net (code "148") (name "unconnected-(IC2L-IO_L3N_T0_DQS_37-PadA9)") (class "Default")
      (node (ref "IC2") (pin "A9") (pinfunction "IO_L3N_T0_DQS_37_A9") (pintype "bidirectional"))
    )
    (net (code "149") (name "unconnected-(IC2L-IO_L3P_T0_DQS_37-PadB9)") (class "Default")
      (node (ref "IC2") (pin "B9") (pinfunction "IO_L3P_T0_DQS_37_B9") (pintype "bidirectional"))
    )
    (net (code "150") (name "unconnected-(IC2L-IO_L4N_T0_37-PadA10)") (class "Default")
      (node (ref "IC2") (pin "A10") (pinfunction "IO_L4N_T0_37_A10") (pintype "bidirectional"))
    )
    (net (code "151") (name "unconnected-(IC2L-IO_L4P_T0_37-PadB10)") (class "Default")
      (node (ref "IC2") (pin "B10") (pinfunction "IO_L4P_T0_37_B10") (pintype "bidirectional"))
    )
    (net (code "152") (name "unconnected-(IC2L-IO_L5N_T0_37-PadD10)") (class "Default")
      (node (ref "IC2") (pin "D10") (pinfunction "IO_L5N_T0_37_D10") (pintype "bidirectional"))
    )
    (net (code "153") (name "unconnected-(IC2L-IO_L5P_T0_37-PadE10)") (class "Default")
      (node (ref "IC2") (pin "E10") (pinfunction "IO_L5P_T0_37_E10") (pintype "bidirectional"))
    )
    (net (code "154") (name "unconnected-(IC2L-IO_L6N_T0_VREF_37-PadC9)") (class "Default")
      (node (ref "IC2") (pin "C9") (pinfunction "IO_L6N_T0_VREF_37_C9") (pintype "bidirectional"))
    )
    (net (code "155") (name "unconnected-(IC2L-IO_L6P_T0_37-PadD9)") (class "Default")
      (node (ref "IC2") (pin "D9") (pinfunction "IO_L6P_T0_37_D9") (pintype "bidirectional"))
    )
    (net (code "156") (name "unconnected-(IC2L-IO_L7N_T1_37-PadB6)") (class "Default")
      (node (ref "IC2") (pin "B6") (pinfunction "IO_L7N_T1_37_B6") (pintype "bidirectional"))
    )
    (net (code "157") (name "unconnected-(IC2L-IO_L7P_T1_37-PadB7)") (class "Default")
      (node (ref "IC2") (pin "B7") (pinfunction "IO_L7P_T1_37_B7") (pintype "bidirectional"))
    )
    (net (code "158") (name "unconnected-(IC2L-IO_L8N_T1_37-PadA7)") (class "Default")
      (node (ref "IC2") (pin "A7") (pinfunction "IO_L8N_T1_37_A7") (pintype "bidirectional"))
    )
    (net (code "159") (name "unconnected-(IC2L-IO_L8P_T1_37-PadA8)") (class "Default")
      (node (ref "IC2") (pin "A8") (pinfunction "IO_L8P_T1_37_A8") (pintype "bidirectional"))
    )
    (net (code "160") (name "unconnected-(IC2L-IO_L9N_T1_DQS_37-PadF8)") (class "Default")
      (node (ref "IC2") (pin "F8") (pinfunction "IO_L9N_T1_DQS_37_F8") (pintype "bidirectional"))
    )
    (net (code "161") (name "unconnected-(IC2L-IO_L9P_T1_DQS_37-PadF9)") (class "Default")
      (node (ref "IC2") (pin "F9") (pinfunction "IO_L9P_T1_DQS_37_F9") (pintype "bidirectional"))
    )
    (net (code "162") (name "unconnected-(IC2L-IO_L10N_T1_37-PadC8)") (class "Default")
      (node (ref "IC2") (pin "C8") (pinfunction "IO_L10N_T1_37_C8") (pintype "bidirectional"))
    )
    (net (code "163") (name "unconnected-(IC2L-IO_L10P_T1_37-PadD8)") (class "Default")
      (node (ref "IC2") (pin "D8") (pinfunction "IO_L10P_T1_37_D8") (pintype "bidirectional"))
    )
    (net (code "164") (name "unconnected-(IC2L-IO_L11N_T1_SRCC_37-PadE7)") (class "Default")
      (node (ref "IC2") (pin "E7") (pinfunction "IO_L11N_T1_SRCC_37_E7") (pintype "bidirectional"))
    )
    (net (code "165") (name "unconnected-(IC2L-IO_L11P_T1_SRCC_37-PadE8)") (class "Default")
      (node (ref "IC2") (pin "E8") (pinfunction "IO_L11P_T1_SRCC_37_E8") (pintype "bidirectional"))
    )
    (net (code "166") (name "unconnected-(IC2L-IO_L12N_T1_MRCC_37-PadC6)") (class "Default")
      (node (ref "IC2") (pin "C6") (pinfunction "IO_L12N_T1_MRCC_37_C6") (pintype "bidirectional"))
    )
    (net (code "167") (name "unconnected-(IC2L-IO_L12P_T1_MRCC_37-PadC7)") (class "Default")
      (node (ref "IC2") (pin "C7") (pinfunction "IO_L12P_T1_MRCC_37_C7") (pintype "bidirectional"))
    )
    (net (code "168") (name "unconnected-(IC2L-IO_L13N_T2_MRCC_37-PadD5)") (class "Default")
      (node (ref "IC2") (pin "D5") (pinfunction "IO_L13N_T2_MRCC_37_D5") (pintype "bidirectional"))
    )
    (net (code "169") (name "unconnected-(IC2L-IO_L13P_T2_MRCC_37-PadD6)") (class "Default")
      (node (ref "IC2") (pin "D6") (pinfunction "IO_L13P_T2_MRCC_37_D6") (pintype "bidirectional"))
    )
    (net (code "170") (name "unconnected-(IC2L-IO_L14N_T2_SRCC_37-PadE5)") (class "Default")
      (node (ref "IC2") (pin "E5") (pinfunction "IO_L14N_T2_SRCC_37_E5") (pintype "bidirectional"))
    )
    (net (code "171") (name "unconnected-(IC2L-IO_L14P_T2_SRCC_37-PadE6)") (class "Default")
      (node (ref "IC2") (pin "E6") (pinfunction "IO_L14P_T2_SRCC_37_E6") (pintype "bidirectional"))
    )
    (net (code "172") (name "unconnected-(IC2L-IO_L15N_T2_DQS_37-PadA4)") (class "Default")
      (node (ref "IC2") (pin "A4") (pinfunction "IO_L15N_T2_DQS_37_A4") (pintype "bidirectional"))
    )
    (net (code "173") (name "unconnected-(IC2L-IO_L15P_T2_DQS_37-PadB4)") (class "Default")
      (node (ref "IC2") (pin "B4") (pinfunction "IO_L15P_T2_DQS_37_B4") (pintype "bidirectional"))
    )
    (net (code "174") (name "unconnected-(IC2L-IO_L16N_T2_37-PadA5)") (class "Default")
      (node (ref "IC2") (pin "A5") (pinfunction "IO_L16N_T2_37_A5") (pintype "bidirectional"))
    )
    (net (code "175") (name "unconnected-(IC2L-IO_L16P_T2_37-PadB5)") (class "Default")
      (node (ref "IC2") (pin "B5") (pinfunction "IO_L16P_T2_37_B5") (pintype "bidirectional"))
    )
    (net (code "176") (name "unconnected-(IC2L-IO_L17N_T2_37-PadC4)") (class "Default")
      (node (ref "IC2") (pin "C4") (pinfunction "IO_L17N_T2_37_C4") (pintype "bidirectional"))
    )
    (net (code "177") (name "unconnected-(IC2L-IO_L17P_T2_37-PadD4)") (class "Default")
      (node (ref "IC2") (pin "D4") (pinfunction "IO_L17P_T2_37_D4") (pintype "bidirectional"))
    )
    (net (code "178") (name "unconnected-(IC2L-IO_L18N_T2_37-PadF4)") (class "Default")
      (node (ref "IC2") (pin "F4") (pinfunction "IO_L18N_T2_37_F4") (pintype "bidirectional"))
    )
    (net (code "179") (name "unconnected-(IC2L-IO_L18P_T2_37-PadF5)") (class "Default")
      (node (ref "IC2") (pin "F5") (pinfunction "IO_L18P_T2_37_F5") (pintype "bidirectional"))
    )
    (net (code "180") (name "unconnected-(IC2L-IO_L19N_T3_VREF_37-PadC3)") (class "Default")
      (node (ref "IC2") (pin "C3") (pinfunction "IO_L19N_T3_VREF_37_C3") (pintype "bidirectional"))
    )
    (net (code "181") (name "unconnected-(IC2L-IO_L19P_T3_37-PadD3)") (class "Default")
      (node (ref "IC2") (pin "D3") (pinfunction "IO_L19P_T3_37_D3") (pintype "bidirectional"))
    )
    (net (code "182") (name "unconnected-(IC2L-IO_L20N_T3_37-PadA2)") (class "Default")
      (node (ref "IC2") (pin "A2") (pinfunction "IO_L20N_T3_37_A2") (pintype "bidirectional"))
    )
    (net (code "183") (name "unconnected-(IC2L-IO_L20P_T3_37-PadA3)") (class "Default")
      (node (ref "IC2") (pin "A3") (pinfunction "IO_L20P_T3_37_A3") (pintype "bidirectional"))
    )
    (net (code "184") (name "unconnected-(IC2L-IO_L21N_T3_DQS_37-PadB2)") (class "Default")
      (node (ref "IC2") (pin "B2") (pinfunction "IO_L21N_T3_DQS_37_B2") (pintype "bidirectional"))
    )
    (net (code "185") (name "unconnected-(IC2L-IO_L21P_T3_DQS_37-PadC2)") (class "Default")
      (node (ref "IC2") (pin "C2") (pinfunction "IO_L21P_T3_DQS_37_C2") (pintype "bidirectional"))
    )
    (net (code "186") (name "unconnected-(IC2L-IO_L22N_T3_37-PadB1)") (class "Default")
      (node (ref "IC2") (pin "B1") (pinfunction "IO_L22N_T3_37_B1") (pintype "bidirectional"))
    )
    (net (code "187") (name "unconnected-(IC2L-IO_L22P_T3_37-PadC1)") (class "Default")
      (node (ref "IC2") (pin "C1") (pinfunction "IO_L22P_T3_37_C1") (pintype "bidirectional"))
    )
    (net (code "188") (name "unconnected-(IC2L-IO_L23N_T3_37-PadD1)") (class "Default")
      (node (ref "IC2") (pin "D1") (pinfunction "IO_L23N_T3_37_D1") (pintype "bidirectional"))
    )
    (net (code "189") (name "unconnected-(IC2L-IO_L23P_T3_37-PadE1)") (class "Default")
      (node (ref "IC2") (pin "E1") (pinfunction "IO_L23P_T3_37_E1") (pintype "bidirectional"))
    )
    (net (code "190") (name "unconnected-(IC2L-IO_L24N_T3_37-PadE2)") (class "Default")
      (node (ref "IC2") (pin "E2") (pinfunction "IO_L24N_T3_37_E2") (pintype "bidirectional"))
    )
    (net (code "191") (name "unconnected-(IC2L-IO_L24P_T3_37-PadE3)") (class "Default")
      (node (ref "IC2") (pin "E3") (pinfunction "IO_L24P_T3_37_E3") (pintype "bidirectional"))
    )
    (net (code "192") (name "unconnected-(J1-Pada4)") (class "Default")
      (node (ref "J1") (pin "a4") (pinfunction "a4_a4") (pintype "bidirectional"))
    )
    (net (code "193") (name "unconnected-(J1-Pada10)") (class "Default")
      (node (ref "J1") (pin "a10") (pinfunction "a10_a10") (pintype "bidirectional"))
    )
    (net (code "194") (name "unconnected-(J1-Padb4)") (class "Default")
      (node (ref "J1") (pin "b4") (pinfunction "b4_b4") (pintype "bidirectional"))
    )
    (net (code "195") (name "unconnected-(J1-Padb7)") (class "Default")
      (node (ref "J1") (pin "b7") (pinfunction "b7_b7") (pintype "bidirectional"))
    )
    (net (code "196") (name "unconnected-(J1-Padb8)") (class "Default")
      (node (ref "J1") (pin "b8") (pinfunction "b8_b8") (pintype "bidirectional"))
    )
    (net (code "197") (name "unconnected-(J1-Padb9)") (class "Default")
      (node (ref "J1") (pin "b9") (pinfunction "b9_b9") (pintype "bidirectional"))
    )
    (net (code "198") (name "unconnected-(J1-Padb10)") (class "Default")
      (node (ref "J1") (pin "b10") (pinfunction "b10_b10") (pintype "bidirectional"))
    )
    (net (code "199") (name "unconnected-(J1-PadbG4)") (class "Default")
      (node (ref "J1") (pin "bG4") (pinfunction "bG4_bG4") (pintype "power_in"))
    )
    (net (code "200") (name "unconnected-(J1-Padc4)") (class "Default")
      (node (ref "J1") (pin "c4") (pinfunction "c4_c4") (pintype "bidirectional"))
    )
    (net (code "201") (name "unconnected-(J1-Padd4)") (class "Default")
      (node (ref "J1") (pin "d4") (pinfunction "d4_d4") (pintype "bidirectional"))
    )
    (net (code "202") (name "unconnected-(J1-Padd5)") (class "Default")
      (node (ref "J1") (pin "d5") (pinfunction "d5_d5") (pintype "bidirectional"))
    )
    (net (code "203") (name "unconnected-(J1-Padd6)") (class "Default")
      (node (ref "J1") (pin "d6") (pinfunction "d6_d6") (pintype "bidirectional"))
    )
    (net (code "204") (name "unconnected-(J1-Padd7)") (class "Default")
      (node (ref "J1") (pin "d7") (pinfunction "d7_d7") (pintype "bidirectional"))
    )
    (net (code "205") (name "unconnected-(J1-Padd8)") (class "Default")
      (node (ref "J1") (pin "d8") (pinfunction "d8_d8") (pintype "bidirectional"))
    )
    (net (code "206") (name "unconnected-(J1-Padd9)") (class "Default")
      (node (ref "J1") (pin "d9") (pinfunction "d9_d9") (pintype "bidirectional"))
    )
    (net (code "207") (name "unconnected-(J1-Padd10)") (class "Default")
      (node (ref "J1") (pin "d10") (pinfunction "d10_d10") (pintype "bidirectional"))
    )
    (net (code "208") (name "unconnected-(J1-Pade3)") (class "Default")
      (node (ref "J1") (pin "e3") (pinfunction "e3_e3") (pintype "bidirectional"))
    )
    (net (code "209") (name "unconnected-(J1-Pade4)") (class "Default")
      (node (ref "J1") (pin "e4") (pinfunction "e4_e4") (pintype "bidirectional"))
    )
    (net (code "210") (name "unconnected-(J1-Padf3)") (class "Default")
      (node (ref "J1") (pin "f3") (pinfunction "f3_f3") (pintype "bidirectional"))
    )
    (net (code "211") (name "unconnected-(J1-Padf4)") (class "Default")
      (node (ref "J1") (pin "f4") (pinfunction "f4_f4") (pintype "bidirectional"))
    )
    (net (code "212") (name "unconnected-(J2-Pada3)") (class "Default")
      (node (ref "J2") (pin "a3") (pinfunction "a3_a3") (pintype "bidirectional"))
    )
    (net (code "213") (name "unconnected-(J2-Pada4)") (class "Default")
      (node (ref "J2") (pin "a4") (pinfunction "a4_a4") (pintype "bidirectional"))
    )
    (net (code "214") (name "unconnected-(J2-Pada6)") (class "Default")
      (node (ref "J2") (pin "a6") (pinfunction "a6_a6") (pintype "bidirectional"))
    )
    (net (code "215") (name "unconnected-(J2-Pada7)") (class "Default")
      (node (ref "J2") (pin "a7") (pinfunction "a7_a7") (pintype "bidirectional"))
    )
    (net (code "216") (name "unconnected-(J2-Pada8)") (class "Default")
      (node (ref "J2") (pin "a8") (pinfunction "a8_a8") (pintype "bidirectional"))
    )
    (net (code "217") (name "unconnected-(J2-Pada10)") (class "Default")
      (node (ref "J2") (pin "a10") (pinfunction "a10_a10") (pintype "bidirectional"))
    )
    (net (code "218") (name "unconnected-(J2-Padb1)") (class "Default")
      (node (ref "J2") (pin "b1") (pinfunction "b1_b1") (pintype "bidirectional"))
    )
    (net (code "219") (name "unconnected-(J2-Padb2)") (class "Default")
      (node (ref "J2") (pin "b2") (pinfunction "b2_b2") (pintype "bidirectional"))
    )
    (net (code "220") (name "unconnected-(J2-Padb3)") (class "Default")
      (node (ref "J2") (pin "b3") (pinfunction "b3_b3") (pintype "bidirectional"))
    )
    (net (code "221") (name "unconnected-(J2-Padb4)") (class "Default")
      (node (ref "J2") (pin "b4") (pinfunction "b4_b4") (pintype "bidirectional"))
    )
    (net (code "222") (name "unconnected-(J2-Padb6)") (class "Default")
      (node (ref "J2") (pin "b6") (pinfunction "b6_b6") (pintype "bidirectional"))
    )
    (net (code "223") (name "unconnected-(J2-Padb7)") (class "Default")
      (node (ref "J2") (pin "b7") (pinfunction "b7_b7") (pintype "bidirectional"))
    )
    (net (code "224") (name "unconnected-(J2-Padb8)") (class "Default")
      (node (ref "J2") (pin "b8") (pinfunction "b8_b8") (pintype "bidirectional"))
    )
    (net (code "225") (name "unconnected-(J2-Padb10)") (class "Default")
      (node (ref "J2") (pin "b10") (pinfunction "b10_b10") (pintype "bidirectional"))
    )
    (net (code "226") (name "unconnected-(J2-Padd1)") (class "Default")
      (node (ref "J2") (pin "d1") (pinfunction "d1_d1") (pintype "bidirectional"))
    )
    (net (code "227") (name "unconnected-(J2-Padd2)") (class "Default")
      (node (ref "J2") (pin "d2") (pinfunction "d2_d2") (pintype "bidirectional"))
    )
    (net (code "228") (name "unconnected-(J2-Padf1)") (class "Default")
      (node (ref "J2") (pin "f1") (pinfunction "f1_f1") (pintype "bidirectional"))
    )
    (net (code "229") (name "unconnected-(J2-Padf2)") (class "Default")
      (node (ref "J2") (pin "f2") (pinfunction "f2_f2") (pintype "bidirectional"))
    )
  )
)
